# WeatherBoard.net
KiCad netlist of a schematic drawn in EAGLE
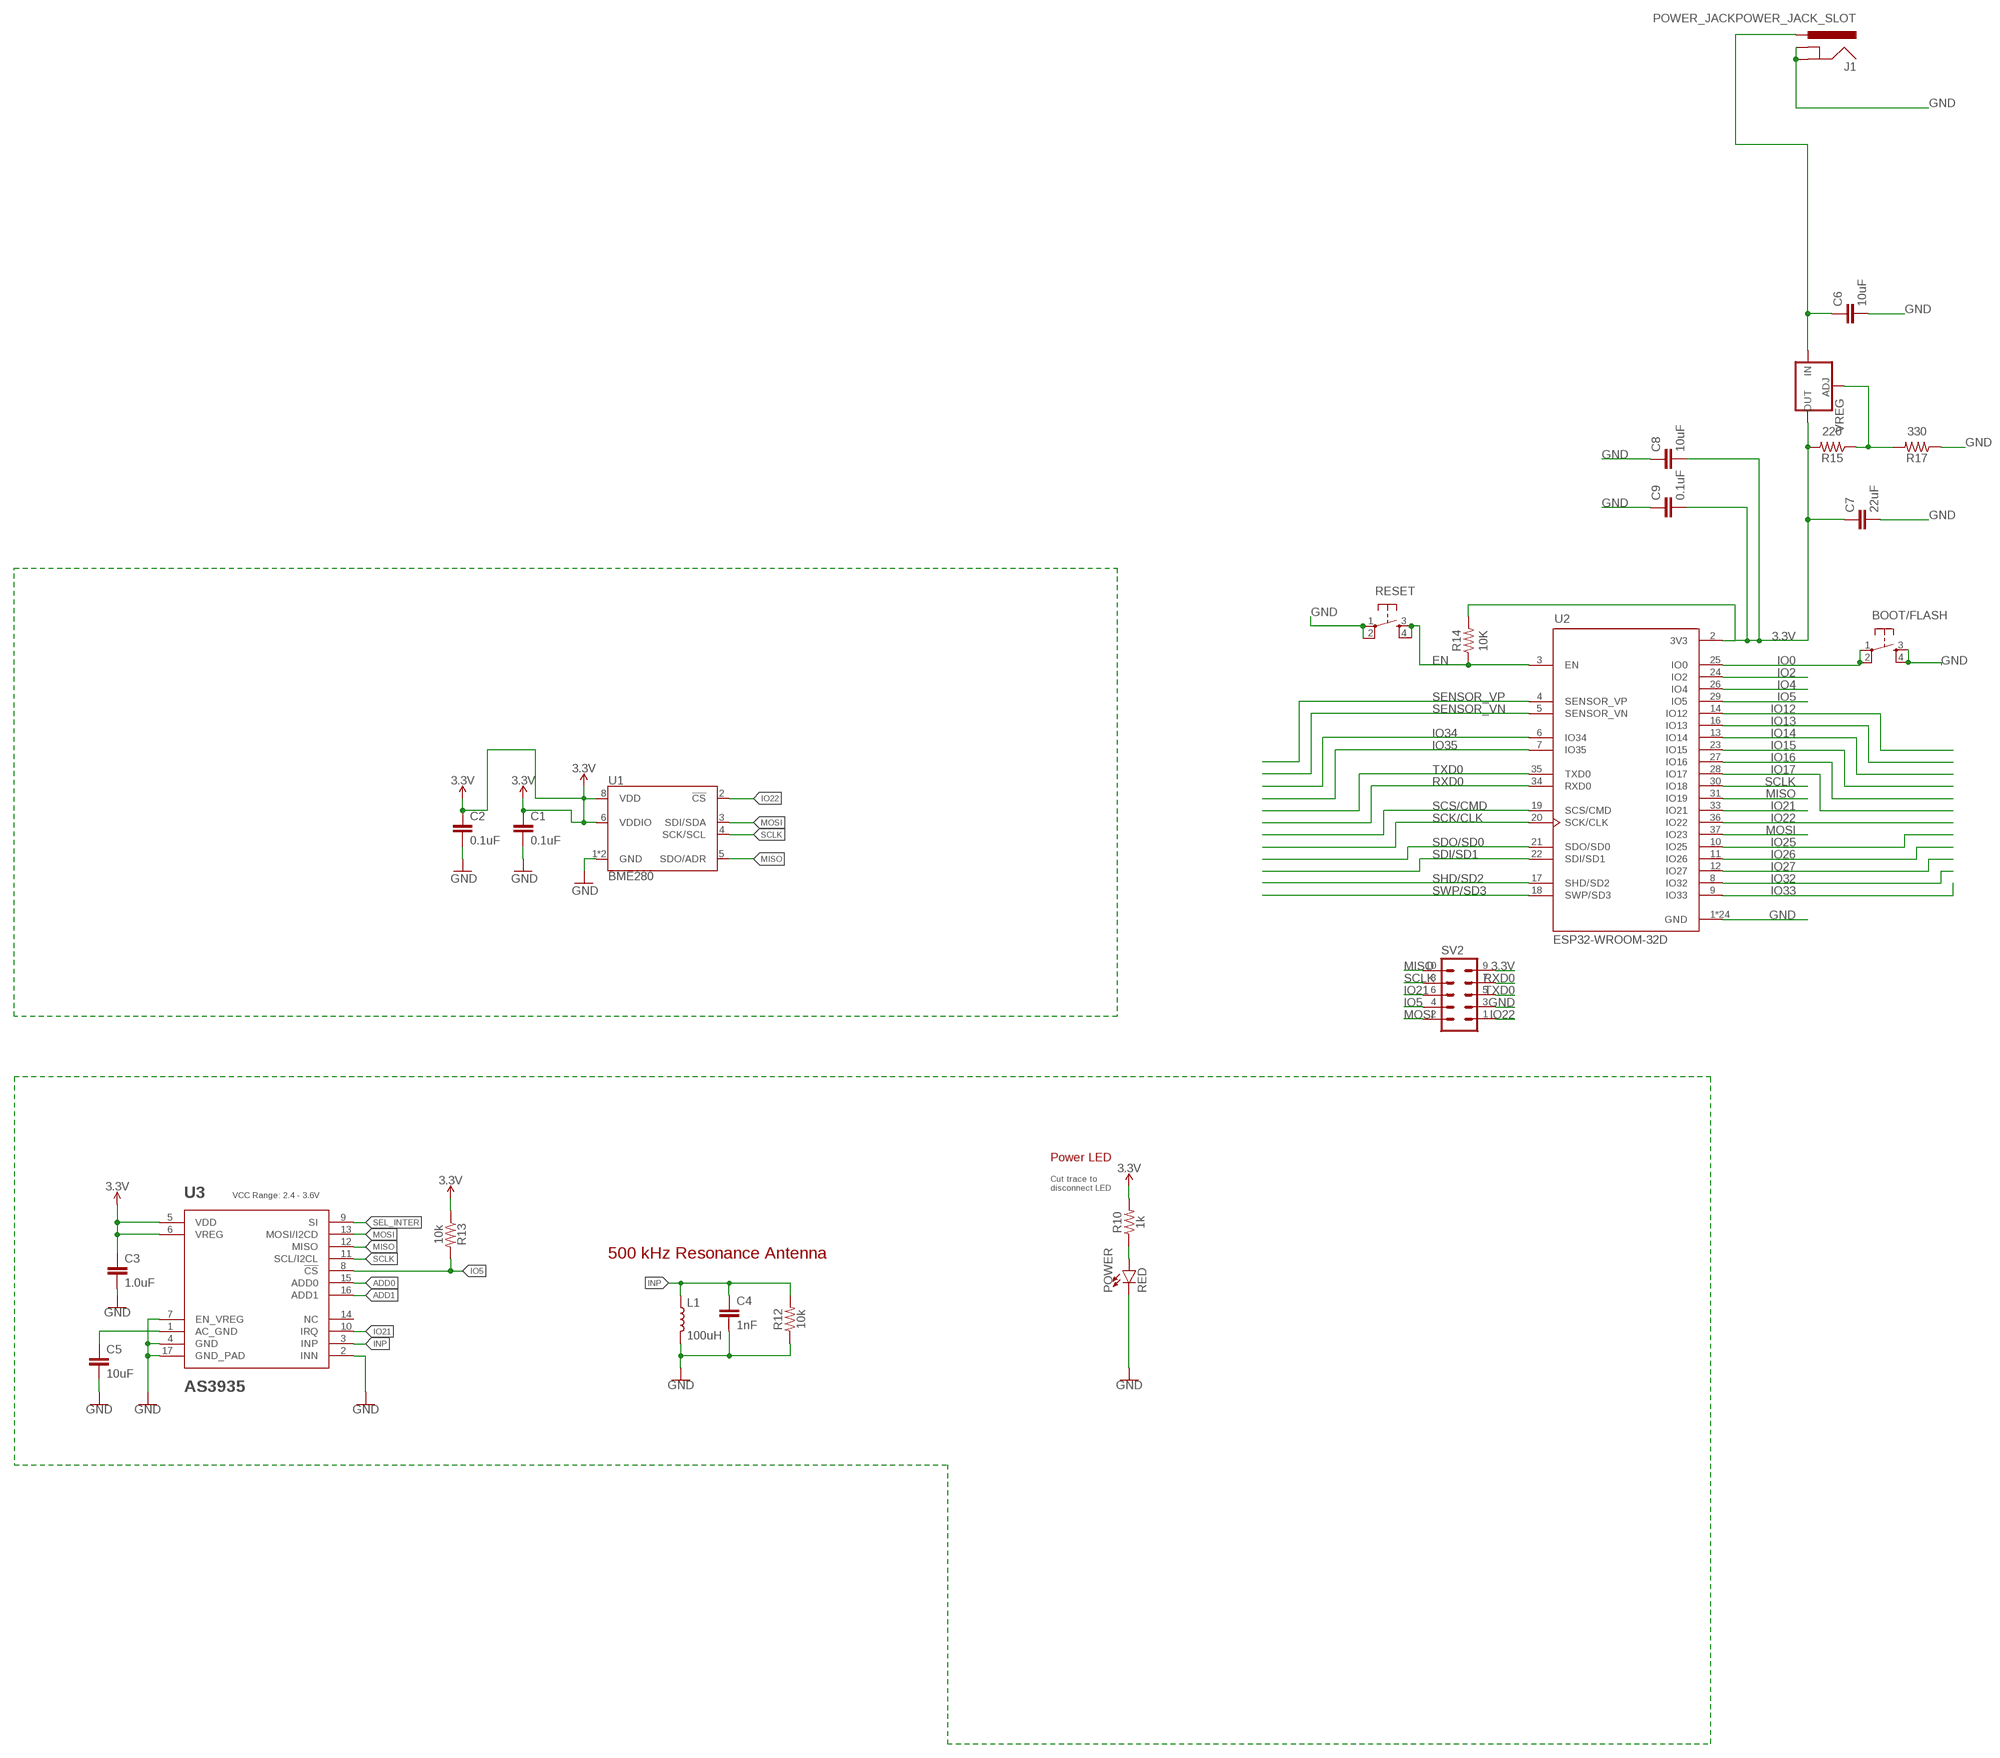
[diagram p0: schematic, sheet 1]

(export (version "E")
  (design (tool "Eeschema 10.0.6"))
  (components
    (comp (ref "BOOT/FLASH")
      (value "TAC_SWITCHPTH")
      (footprint "eagle-import:TACTILE-PTH")
      (libsource (lib "eagle-import") (part "TAC_SWITCHPTH"))
    )
    (comp (ref "C1")
      (value "0.1uF")
      (footprint "eagle-import:0603")
      (libsource (lib "eagle-import") (part "0.1UF-0603-25V-(+80/-20%)"))
    )
    (comp (ref "C2")
      (value "0.1uF")
      (footprint "eagle-import:0603")
      (libsource (lib "eagle-import") (part "0.1UF-0603-25V-(+80/-20%)"))
    )
    (comp (ref "C3")
      (value "1.0uF")
      (footprint "eagle-import:0603")
      (libsource (lib "eagle-import") (part "1.0UF-0603-16V-10%"))
    )
    (comp (ref "C4")
      (value "1nF")
      (footprint "eagle-import:0603")
      (libsource (lib "eagle-import") (part "1.0NF/1000PF-0603-50V-10%"))
    )
    (comp (ref "C5")
      (value "10uF")
      (footprint "eagle-import:0603")
      (libsource (lib "eagle-import") (part "10UF-0603-6.3V-20%"))
    )
    (comp (ref "C6")
      (value "10uF")
      (footprint "eagle-import:0603")
      (libsource (lib "eagle-import") (part "10UF-0603-6.3V-20%"))
    )
    (comp (ref "C7")
      (value "22uF")
      (footprint "eagle-import:0603")
      (libsource (lib "eagle-import") (part "22NF/22,000PF-0603-50V-10%"))
    )
    (comp (ref "C8")
      (value "10uF")
      (footprint "eagle-import:0603")
      (libsource (lib "eagle-import") (part "10UF-0603-6.3V-20%"))
    )
    (comp (ref "C9")
      (value "0.1uF")
      (footprint "eagle-import:0603")
      (libsource (lib "eagle-import") (part "0.1UF-0603-25V-(+80/-20%)"))
    )
    (comp (ref "J1")
      (value "POWER_JACKPOWER_JACK_SLOT")
      (footprint "eagle-import:POWER_JACK_PTH_SLOT")
      (libsource (lib "eagle-import") (part "POWER_JACKPOWER_JACK_SLOT"))
    )
    (comp (ref "L1")
      (value "100uH")
      (footprint "eagle-import:MA5532-AE")
      (libsource (lib "eagle-import") (part "MA5532-AE"))
    )
    (comp (ref "POWER")
      (value "RED")
      (footprint "eagle-import:LED-0603")
      (libsource (lib "eagle-import") (part "LED-RED0603"))
    )
    (comp (ref "R10")
      (value "1k")
      (footprint "eagle-import:0603")
      (libsource (lib "eagle-import") (part "1KOHM-0603-1/10W-1%"))
    )
    (comp (ref "R12")
      (value "10k")
      (footprint "eagle-import:0603")
      (libsource (lib "eagle-import") (part "10KOHM-0603-1/10W-1%"))
    )
    (comp (ref "R13")
      (value "10k")
      (footprint "eagle-import:0603")
      (libsource (lib "eagle-import") (part "10KOHM-0603-1/10W-1%"))
    )
    (comp (ref "R14")
      (value "10K")
      (footprint "eagle-import:0603")
      (libsource (lib "eagle-import") (part "1.8MOHM"))
    )
    (comp (ref "R15")
      (value "220")
      (footprint "eagle-import:0603")
      (libsource (lib "eagle-import") (part "1.8MOHM"))
    )
    (comp (ref "R17")
      (value "330")
      (footprint "eagle-import:0603")
      (libsource (lib "eagle-import") (part "1.8MOHM"))
    )
    (comp (ref "RESET")
      (value "TAC_SWITCHPTH")
      (footprint "eagle-import:TACTILE-PTH")
      (libsource (lib "eagle-import") (part "TAC_SWITCHPTH"))
    )
    (comp (ref "SV2")
      (value "MA05-2")
      (footprint "eagle-import:MA05-2")
      (libsource (lib "eagle-import") (part "MA05-2"))
    )
    (comp (ref "U1")
      (value "BME280")
      (footprint "eagle-import:LGA-8-2.5X2.5")
      (libsource (lib "eagle-import") (part "BME280"))
    )
    (comp (ref "U2")
      (value "ESP32-WROOM-32D")
      (footprint "eagle-import:MODULE_ESP32-WROOM-32D")
      (fields (field (name "MF") "Espressif Systems"))
      (libsource (lib "eagle-import") (part "ESP32-WROOM-32D"))
    )
    (comp (ref "U3")
      (value "AS3935")
      (footprint "eagle-import:16LD_MLPQ")
      (libsource (lib "eagle-import") (part "AS3935QFN"))
    )
    (comp (ref "VREG")
      (value "ADJWEATHERSTATION")
      (footprint "eagle-import:VREG_NCP1117STAT3G")
      (libsource (lib "eagle-import") (part "ADJWEATHERSTATION"))
    )
  )
  (nets
    (net (code "1") (name "/EN") (class "Default")
      (node (ref "R14") (pin "1") (pinfunction "1_1") (pintype "passive"))
      (node (ref "RESET") (pin "3") (pinfunction "3_3") (pintype "passive"))
      (node (ref "RESET") (pin "4") (pinfunction "4_4") (pintype "passive"))
      (node (ref "U2") (pin "3") (pinfunction "EN_3") (pintype "input"))
    )
    (net (code "2") (name "/IO0") (class "Default")
      (node (ref "BOOT/FLASH") (pin "1") (pinfunction "1_1") (pintype "passive"))
      (node (ref "BOOT/FLASH") (pin "2") (pinfunction "2_2") (pintype "passive"))
      (node (ref "U2") (pin "25") (pinfunction "IO0_25") (pintype "bidirectional"))
    )
    (net (code "3") (name "/IO2") (class "Default")
      (node (ref "U2") (pin "24") (pinfunction "IO2_24") (pintype "bidirectional"))
    )
    (net (code "4") (name "/IO4") (class "Default")
      (node (ref "U2") (pin "26") (pinfunction "IO4_26") (pintype "bidirectional"))
    )
    (net (code "5") (name "/IO12") (class "Default")
      (node (ref "U2") (pin "14") (pinfunction "IO12_14") (pintype "bidirectional"))
    )
    (net (code "6") (name "/IO13") (class "Default")
      (node (ref "U2") (pin "16") (pinfunction "IO13_16") (pintype "bidirectional"))
    )
    (net (code "7") (name "/IO14") (class "Default")
      (node (ref "U2") (pin "13") (pinfunction "IO14_13") (pintype "bidirectional"))
    )
    (net (code "8") (name "/IO15") (class "Default")
      (node (ref "U2") (pin "23") (pinfunction "IO15_23") (pintype "bidirectional"))
    )
    (net (code "9") (name "/IO16") (class "Default")
      (node (ref "U2") (pin "27") (pinfunction "IO16_27") (pintype "bidirectional"))
    )
    (net (code "10") (name "/IO17") (class "Default")
      (node (ref "U2") (pin "28") (pinfunction "IO17_28") (pintype "bidirectional"))
    )
    (net (code "11") (name "/IO25") (class "Default")
      (node (ref "U2") (pin "10") (pinfunction "IO25_10") (pintype "bidirectional"))
    )
    (net (code "12") (name "/IO26") (class "Default")
      (node (ref "U2") (pin "11") (pinfunction "IO26_11") (pintype "bidirectional"))
    )
    (net (code "13") (name "/IO27") (class "Default")
      (node (ref "U2") (pin "12") (pinfunction "IO27_12") (pintype "bidirectional"))
    )
    (net (code "14") (name "/IO32") (class "Default")
      (node (ref "U2") (pin "8") (pinfunction "IO32_8") (pintype "bidirectional"))
    )
    (net (code "15") (name "/IO33") (class "Default")
      (node (ref "U2") (pin "9") (pinfunction "IO33_9") (pintype "bidirectional"))
    )
    (net (code "16") (name "/IO34") (class "Default")
      (node (ref "U2") (pin "6") (pinfunction "IO34_6") (pintype "input"))
    )
    (net (code "17") (name "/IO35") (class "Default")
      (node (ref "U2") (pin "7") (pinfunction "IO35_7") (pintype "input"))
    )
    (net (code "18") (name "/RXD0") (class "Default")
      (node (ref "SV2") (pin "7") (pinfunction "7_7") (pintype "passive"))
      (node (ref "U2") (pin "34") (pinfunction "RXD0_34") (pintype "bidirectional"))
    )
    (net (code "19") (name "/SCK{slash}CLK") (class "Default")
      (node (ref "U2") (pin "20") (pinfunction "SCK/CLK_20") (pintype "bidirectional"))
    )
    (net (code "20") (name "/SCS{slash}CMD") (class "Default")
      (node (ref "U2") (pin "19") (pinfunction "SCS/CMD_19") (pintype "bidirectional"))
    )
    (net (code "21") (name "/SDI{slash}SD1") (class "Default")
      (node (ref "U2") (pin "22") (pinfunction "SDI/SD1_22") (pintype "bidirectional"))
    )
    (net (code "22") (name "/SDO{slash}SD0") (class "Default")
      (node (ref "U2") (pin "21") (pinfunction "SDO/SD0_21") (pintype "bidirectional"))
    )
    (net (code "23") (name "/SENSOR_VN") (class "Default")
      (node (ref "U2") (pin "5") (pinfunction "SENSOR_VN_5") (pintype "input"))
    )
    (net (code "24") (name "/SENSOR_VP") (class "Default")
      (node (ref "U2") (pin "4") (pinfunction "SENSOR_VP_4") (pintype "input"))
    )
    (net (code "25") (name "/SHD{slash}SD2") (class "Default")
      (node (ref "U2") (pin "17") (pinfunction "SHD/SD2_17") (pintype "bidirectional"))
    )
    (net (code "26") (name "/SWP{slash}SD3") (class "Default")
      (node (ref "U2") (pin "18") (pinfunction "SWP/SD3_18") (pintype "bidirectional"))
    )
    (net (code "27") (name "/TXD0") (class "Default")
      (node (ref "SV2") (pin "5") (pinfunction "5_5") (pintype "passive"))
      (node (ref "U2") (pin "35") (pinfunction "TXD0_35") (pintype "bidirectional"))
    )
    (net (code "28") (name "3.3V") (class "Default")
      (node (ref "C1") (pin "1") (pinfunction "1_1") (pintype "passive"))
      (node (ref "C2") (pin "1") (pinfunction "1_1") (pintype "passive"))
      (node (ref "C3") (pin "1") (pinfunction "1_1") (pintype "passive"))
      (node (ref "C7") (pin "1") (pinfunction "1_1") (pintype "passive"))
      (node (ref "C8") (pin "2") (pinfunction "2_2") (pintype "passive"))
      (node (ref "C9") (pin "2") (pinfunction "2_2") (pintype "passive"))
      (node (ref "R10") (pin "2") (pinfunction "2_2") (pintype "passive"))
      (node (ref "R13") (pin "1") (pinfunction "1_1") (pintype "passive"))
      (node (ref "R14") (pin "2") (pinfunction "2_2") (pintype "passive"))
      (node (ref "R15") (pin "2") (pinfunction "2_2") (pintype "passive"))
      (node (ref "SV2") (pin "9") (pinfunction "9_9") (pintype "passive"))
      (node (ref "U1") (pin "6") (pinfunction "VDDIO_6") (pintype "bidirectional"))
      (node (ref "U1") (pin "8") (pinfunction "VDD_8") (pintype "bidirectional"))
      (node (ref "U2") (pin "2") (pinfunction "3V3_2") (pintype "power_in"))
      (node (ref "U3") (pin "5") (pinfunction "VDD_5") (pintype "power_in"))
      (node (ref "U3") (pin "6") (pinfunction "VREG_6") (pintype "power_in"))
      (node (ref "VREG") (pin "2") (pinfunction "OUT_2") (pintype "output"))
      (node (ref "VREG") (pin "4") (pinfunction "OUT_4") (pintype "output"))
    )
    (net (code "29") (name "ADD0") (class "Default")
      (node (ref "U3") (pin "15") (pinfunction "ADD0_15") (pintype "input"))
    )
    (net (code "30") (name "ADD1") (class "Default")
      (node (ref "U3") (pin "16") (pinfunction "ADD1_16") (pintype "input"))
    )
    (net (code "31") (name "GND") (class "Default")
      (node (ref "BOOT/FLASH") (pin "3") (pinfunction "3_3") (pintype "passive"))
      (node (ref "BOOT/FLASH") (pin "4") (pinfunction "4_4") (pintype "passive"))
      (node (ref "C1") (pin "2") (pinfunction "2_2") (pintype "passive"))
      (node (ref "C2") (pin "2") (pinfunction "2_2") (pintype "passive"))
      (node (ref "C3") (pin "2") (pinfunction "2_2") (pintype "passive"))
      (node (ref "C4") (pin "2") (pinfunction "2_2") (pintype "passive"))
      (node (ref "C5") (pin "2") (pinfunction "2_2") (pintype "passive"))
      (node (ref "C6") (pin "2") (pinfunction "2_2") (pintype "passive"))
      (node (ref "C7") (pin "2") (pinfunction "2_2") (pintype "passive"))
      (node (ref "C8") (pin "1") (pinfunction "1_1") (pintype "passive"))
      (node (ref "C9") (pin "1") (pinfunction "1_1") (pintype "passive"))
      (node (ref "J1") (pin "GND") (pinfunction "GND_GND") (pintype "bidirectional"))
      (node (ref "J1") (pin "GNDBREAK") (pinfunction "GNDBREAK_GNDBREAK") (pintype "bidirectional"))
      (node (ref "L1") (pin "2") (pinfunction "2_2") (pintype "passive"))
      (node (ref "POWER") (pin "C") (pinfunction "C_C") (pintype "passive"))
      (node (ref "R12") (pin "1") (pinfunction "1_1") (pintype "passive"))
      (node (ref "R17") (pin "1") (pinfunction "1_1") (pintype "passive"))
      (node (ref "RESET") (pin "1") (pinfunction "1_1") (pintype "passive"))
      (node (ref "RESET") (pin "2") (pinfunction "2_2") (pintype "passive"))
      (node (ref "SV2") (pin "3") (pinfunction "3_3") (pintype "passive"))
      (node (ref "U1") (pin "1") (pinfunction "GND_1") (pintype "bidirectional"))
      (node (ref "U1") (pin "7") (pinfunction "GND_7") (pintype "bidirectional"))
      (node (ref "U2") (pin "1") (pinfunction "GND_1") (pintype "power_in"))
      (node (ref "U2") (pin "15") (pinfunction "GND_15") (pintype "power_in"))
      (node (ref "U2") (pin "38") (pinfunction "GND_38") (pintype "power_in"))
      (node (ref "U2") (pin "39_1") (pinfunction "GND_39_1") (pintype "power_in"))
      (node (ref "U2") (pin "39_10") (pinfunction "GND_39_10") (pintype "power_in"))
      (node (ref "U2") (pin "39_11") (pinfunction "GND_39_11") (pintype "power_in"))
      (node (ref "U2") (pin "39_12") (pinfunction "GND_39_12") (pintype "power_in"))
      (node (ref "U2") (pin "39_13") (pinfunction "GND_39_13") (pintype "power_in"))
      (node (ref "U2") (pin "39_14") (pinfunction "GND_39_14") (pintype "power_in"))
      (node (ref "U2") (pin "39_15") (pinfunction "GND_39_15") (pintype "power_in"))
      (node (ref "U2") (pin "39_16") (pinfunction "GND_39_16") (pintype "power_in"))
      (node (ref "U2") (pin "39_17") (pinfunction "GND_39_17") (pintype "power_in"))
      (node (ref "U2") (pin "39_18") (pinfunction "GND_39_18") (pintype "power_in"))
      (node (ref "U2") (pin "39_19") (pinfunction "GND_39_19") (pintype "power_in"))
      (node (ref "U2") (pin "39_2") (pinfunction "GND_39_2") (pintype "power_in"))
      (node (ref "U2") (pin "39_20") (pinfunction "GND_39_20") (pintype "power_in"))
      (node (ref "U2") (pin "39_21") (pinfunction "GND_39_21") (pintype "power_in"))
      (node (ref "U2") (pin "39_3") (pinfunction "GND_39_3") (pintype "power_in"))
      (node (ref "U2") (pin "39_4") (pinfunction "GND_39_4") (pintype "power_in"))
      (node (ref "U2") (pin "39_5") (pinfunction "GND_39_5") (pintype "power_in"))
      (node (ref "U2") (pin "39_6") (pinfunction "GND_39_6") (pintype "power_in"))
      (node (ref "U2") (pin "39_7") (pinfunction "GND_39_7") (pintype "power_in"))
      (node (ref "U2") (pin "39_8") (pinfunction "GND_39_8") (pintype "power_in"))
      (node (ref "U2") (pin "39_9") (pinfunction "GND_39_9") (pintype "power_in"))
      (node (ref "U3") (pin "17") (pinfunction "GND_PAD_17") (pintype "power_in"))
      (node (ref "U3") (pin "2") (pinfunction "INN_2") (pintype "bidirectional"))
      (node (ref "U3") (pin "4") (pinfunction "GND_4") (pintype "power_in"))
      (node (ref "U3") (pin "7") (pinfunction "EN_VREG_7") (pintype "bidirectional"))
    )
    (net (code "32") (name "INP") (class "Default")
      (node (ref "C4") (pin "1") (pinfunction "1_1") (pintype "passive"))
      (node (ref "L1") (pin "1") (pinfunction "1_1") (pintype "passive"))
      (node (ref "R12") (pin "2") (pinfunction "2_2") (pintype "passive"))
      (node (ref "U3") (pin "3") (pinfunction "INP_3") (pintype "bidirectional"))
    )
    (net (code "33") (name "IO5") (class "Default")
      (node (ref "R13") (pin "2") (pinfunction "2_2") (pintype "passive"))
      (node (ref "SV2") (pin "4") (pinfunction "4_4") (pintype "passive"))
      (node (ref "U2") (pin "29") (pinfunction "IO5_29") (pintype "bidirectional"))
      (node (ref "U3") (pin "8") (pinfunction "~{CS}_8") (pintype "input"))
    )
    (net (code "34") (name "IO21") (class "Default")
      (node (ref "SV2") (pin "6") (pinfunction "6_6") (pintype "passive"))
      (node (ref "U2") (pin "33") (pinfunction "IO21_33") (pintype "bidirectional"))
      (node (ref "U3") (pin "10") (pinfunction "IRQ_10") (pintype "bidirectional"))
    )
    (net (code "35") (name "IO22") (class "Default")
      (node (ref "SV2") (pin "1") (pinfunction "1_1") (pintype "passive"))
      (node (ref "U1") (pin "2") (pinfunction "~{CS}_2") (pintype "bidirectional"))
      (node (ref "U2") (pin "36") (pinfunction "IO22_36") (pintype "bidirectional"))
    )
    (net (code "36") (name "MISO") (class "Default")
      (node (ref "SV2") (pin "10") (pinfunction "10_10") (pintype "passive"))
      (node (ref "U1") (pin "5") (pinfunction "SDO/ADR_5") (pintype "bidirectional"))
      (node (ref "U2") (pin "31") (pinfunction "IO19_31") (pintype "bidirectional"))
      (node (ref "U3") (pin "12") (pinfunction "MISO_12") (pintype "output"))
    )
    (net (code "37") (name "MOSI") (class "Default")
      (node (ref "SV2") (pin "2") (pinfunction "2_2") (pintype "passive"))
      (node (ref "U1") (pin "3") (pinfunction "SDI/SDA_3") (pintype "bidirectional"))
      (node (ref "U2") (pin "37") (pinfunction "IO23_37") (pintype "bidirectional"))
      (node (ref "U3") (pin "13") (pinfunction "MOSI/I2CD_13") (pintype "input"))
    )
    (net (code "38") (name "Net-(POWER-PadA)") (class "Default")
      (node (ref "POWER") (pin "A") (pinfunction "A_A") (pintype "passive"))
      (node (ref "R10") (pin "1") (pinfunction "1_1") (pintype "passive"))
    )
    (net (code "39") (name "Net-(U3-AC_GND)") (class "Default")
      (node (ref "C5") (pin "1") (pinfunction "1_1") (pintype "passive"))
      (node (ref "U3") (pin "1") (pinfunction "AC_GND_1") (pintype "power_in"))
    )
    (net (code "40") (name "Net-(VREG-ADJ)") (class "Default")
      (node (ref "R15") (pin "1") (pinfunction "1_1") (pintype "passive"))
      (node (ref "R17") (pin "2") (pinfunction "2_2") (pintype "passive"))
      (node (ref "VREG") (pin "1") (pinfunction "ADJ_1") (pintype "input"))
    )
    (net (code "41") (name "Net-(VREG-IN)") (class "Default")
      (node (ref "C6") (pin "1") (pinfunction "1_1") (pintype "passive"))
      (node (ref "J1") (pin "PWR") (pinfunction "PWR_PWR") (pintype "bidirectional"))
      (node (ref "VREG") (pin "3") (pinfunction "IN_3") (pintype "input"))
    )
    (net (code "42") (name "SCLK") (class "Default")
      (node (ref "SV2") (pin "8") (pinfunction "8_8") (pintype "passive"))
      (node (ref "U1") (pin "4") (pinfunction "SCK/SCL_4") (pintype "bidirectional"))
      (node (ref "U2") (pin "30") (pinfunction "IO18_30") (pintype "bidirectional"))
      (node (ref "U3") (pin "11") (pinfunction "SCL/I2CL_11") (pintype "input"))
    )
    (net (code "43") (name "SEL_INTER") (class "Default")
      (node (ref "U3") (pin "9") (pinfunction "SI_9") (pintype "input"))
    )
    (net (code "44") (name "unconnected-(U3-NC-Pad14)") (class "Default")
      (node (ref "U3") (pin "14") (pinfunction "NC_14") (pintype "no_connect"))
    )
  )
)
